# Circuit_Diagram.net
KiCad netlist of a schematic drawn in EAGLE
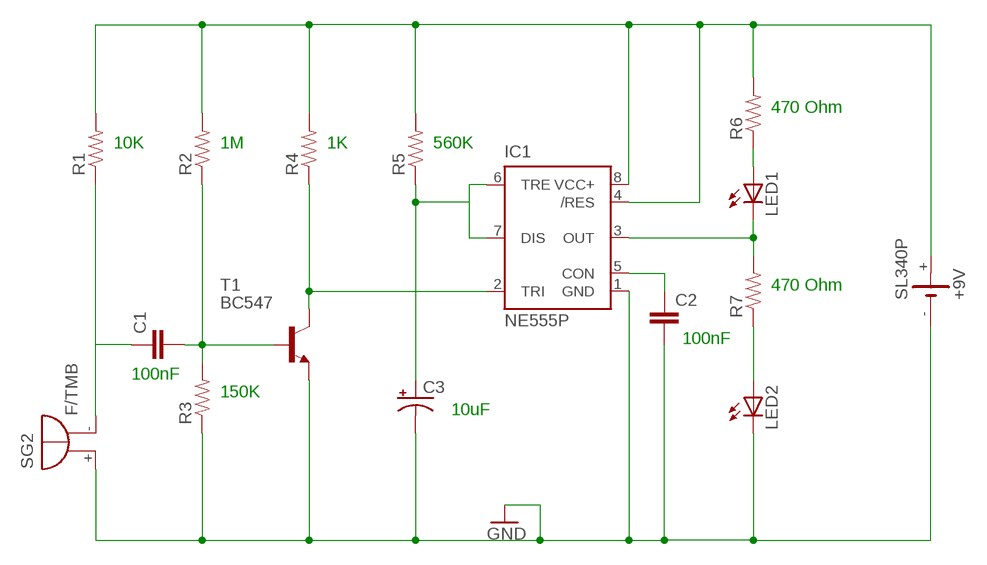
[diagram p0: schematic, sheet 1]

(export (version "E")
  (design (tool "Eeschema 10.0.6"))
  (components
    (comp (ref "+9V")
      (value "SL340P")
      (footprint "eagle-import:SL-340_P3.6V")
      (libsource (lib "eagle-import") (part "SL340P"))
    )
    (comp (ref "C1")
      (value "0.1UF-50V-20%(PTH)KIT-EZ")
      (footprint "eagle-import:CAP-PTH-SMALL-KIT")
      (libsource (lib "eagle-import") (part "0.1UF-50V-20%(PTH)KIT-EZ"))
    )
    (comp (ref "C2")
      (value "0.1UF-50V-20%(PTH)KIT-EZ")
      (footprint "eagle-import:CAP-PTH-SMALL-KIT")
      (libsource (lib "eagle-import") (part "0.1UF-50V-20%(PTH)KIT-EZ"))
    )
    (comp (ref "C3")
      (value "CAP_POLPTH1")
      (footprint "eagle-import:CPOL-RADIAL-100UF-25V")
      (libsource (lib "eagle-import") (part "CAP_POLPTH1"))
    )
    (comp (ref "IC1")
      (value "NE555P")
      (footprint "eagle-import:DIL-08")
      (fields (field (name "MF") "Arrow Electronics") (field (name "MPN") "NE555N"))
      (libsource (lib "eagle-import") (part "NE555P"))
    )
    (comp (ref "LED1")
      (value "LED5MM")
      (footprint "eagle-import:LED5MM")
      (libsource (lib "eagle-import") (part "LED5MM"))
    )
    (comp (ref "LED2")
      (value "LED5MM")
      (footprint "eagle-import:LED5MM")
      (libsource (lib "eagle-import") (part "LED5MM"))
    )
    (comp (ref "R1")
      (value "10KOHM1/6W5%(PTH)KIT")
      (footprint "eagle-import:AXIAL-0.3-KIT")
      (libsource (lib "eagle-import") (part "10KOHM1/6W5%(PTH)KIT"))
    )
    (comp (ref "R2")
      (value "10KOHM1/6W5%(PTH)KIT")
      (footprint "eagle-import:AXIAL-0.3-KIT")
      (libsource (lib "eagle-import") (part "10KOHM1/6W5%(PTH)KIT"))
    )
    (comp (ref "R3")
      (value "10KOHM1/6W5%(PTH)KIT")
      (footprint "eagle-import:AXIAL-0.3-KIT")
      (libsource (lib "eagle-import") (part "10KOHM1/6W5%(PTH)KIT"))
    )
    (comp (ref "R4")
      (value "10KOHM1/6W5%(PTH)KIT")
      (footprint "eagle-import:AXIAL-0.3-KIT")
      (libsource (lib "eagle-import") (part "10KOHM1/6W5%(PTH)KIT"))
    )
    (comp (ref "R5")
      (value "10KOHM1/6W5%(PTH)KIT")
      (footprint "eagle-import:AXIAL-0.3-KIT")
      (libsource (lib "eagle-import") (part "10KOHM1/6W5%(PTH)KIT"))
    )
    (comp (ref "R6")
      (value "10KOHM1/6W5%(PTH)KIT")
      (footprint "eagle-import:AXIAL-0.3-KIT")
      (libsource (lib "eagle-import") (part "10KOHM1/6W5%(PTH)KIT"))
    )
    (comp (ref "R7")
      (value "10KOHM1/6W5%(PTH)KIT")
      (footprint "eagle-import:AXIAL-0.3-KIT")
      (libsource (lib "eagle-import") (part "10KOHM1/6W5%(PTH)KIT"))
    )
    (comp (ref "SG2")
      (value "F/TMB")
      (footprint "eagle-import:F_TMB")
      (libsource (lib "eagle-import") (part "F/TMB"))
    )
    (comp (ref "T1")
      (value "BC547")
      (footprint "eagle-import:TO92")
      (libsource (lib "eagle-import") (part "BC547"))
    )
  )
  (nets
    (net (code "1") (name "GND") (class "Default")
      (node (ref "+9V") (pin "-") (pinfunction "-_-") (pintype "passive"))
      (node (ref "C2") (pin "2") (pinfunction "2_2") (pintype "passive"))
      (node (ref "C3") (pin "2") (pinfunction "-_2") (pintype "passive"))
      (node (ref "IC1") (pin "1") (pinfunction "GND_1") (pintype "power_in"))
      (node (ref "LED2") (pin "K") (pinfunction "C_K") (pintype "passive"))
      (node (ref "R3") (pin "P$1") (pinfunction "1_P$1") (pintype "passive"))
      (node (ref "SG2") (pin "+") (pinfunction "+_+") (pintype "passive"))
      (node (ref "T1") (pin "1") (pinfunction "E_1") (pintype "passive"))
    )
    (net (code "2") (name "Net-(C3-+)") (class "Default")
      (node (ref "C3") (pin "1") (pinfunction "+_1") (pintype "passive"))
      (node (ref "IC1") (pin "6") (pinfunction "TRE_6") (pintype "input"))
      (node (ref "IC1") (pin "7") (pinfunction "DIS_7") (pintype "input"))
      (node (ref "R5") (pin "P$1") (pinfunction "1_P$1") (pintype "passive"))
    )
    (net (code "3") (name "Net-(IC1-CON)") (class "Default")
      (node (ref "C2") (pin "1") (pinfunction "1_1") (pintype "passive"))
      (node (ref "IC1") (pin "5") (pinfunction "CON_5") (pintype "input"))
    )
    (net (code "4") (name "Net-(IC1-OUT)") (class "Default")
      (node (ref "IC1") (pin "3") (pinfunction "OUT_3") (pintype "output"))
      (node (ref "LED1") (pin "K") (pinfunction "C_K") (pintype "passive"))
      (node (ref "R7") (pin "P$2") (pinfunction "2_P$2") (pintype "passive"))
    )
    (net (code "5") (name "Net-(IC1-TRI)") (class "Default")
      (node (ref "IC1") (pin "2") (pinfunction "TRI_2") (pintype "input"))
      (node (ref "R4") (pin "P$1") (pinfunction "1_P$1") (pintype "passive"))
      (node (ref "T1") (pin "3") (pinfunction "C_3") (pintype "passive"))
    )
    (net (code "6") (name "Net-(IC1-VCC+)") (class "Default")
      (node (ref "+9V") (pin "+") (pinfunction "+_+") (pintype "passive"))
      (node (ref "IC1") (pin "4") (pinfunction "/RES_4") (pintype "input"))
      (node (ref "IC1") (pin "8") (pinfunction "VCC+_8") (pintype "power_in"))
      (node (ref "R1") (pin "P$2") (pinfunction "2_P$2") (pintype "passive"))
      (node (ref "R2") (pin "P$2") (pinfunction "2_P$2") (pintype "passive"))
      (node (ref "R4") (pin "P$2") (pinfunction "2_P$2") (pintype "passive"))
      (node (ref "R5") (pin "P$2") (pinfunction "2_P$2") (pintype "passive"))
      (node (ref "R6") (pin "P$2") (pinfunction "2_P$2") (pintype "passive"))
    )
    (net (code "7") (name "Net-(R1-1)") (class "Default")
      (node (ref "C1") (pin "1") (pinfunction "1_1") (pintype "passive"))
      (node (ref "R1") (pin "P$1") (pinfunction "1_P$1") (pintype "passive"))
      (node (ref "SG2") (pin "-") (pinfunction "-_-") (pintype "passive"))
    )
    (net (code "8") (name "Net-(R2-1)") (class "Default")
      (node (ref "C1") (pin "2") (pinfunction "2_2") (pintype "passive"))
      (node (ref "R2") (pin "P$1") (pinfunction "1_P$1") (pintype "passive"))
      (node (ref "R3") (pin "P$2") (pinfunction "2_P$2") (pintype "passive"))
      (node (ref "T1") (pin "2") (pinfunction "B_2") (pintype "passive"))
    )
    (net (code "9") (name "Net-(R6-1)") (class "Default")
      (node (ref "LED1") (pin "A") (pinfunction "A_A") (pintype "passive"))
      (node (ref "R6") (pin "P$1") (pinfunction "1_P$1") (pintype "passive"))
    )
    (net (code "10") (name "Net-(R7-1)") (class "Default")
      (node (ref "LED2") (pin "A") (pinfunction "A_A") (pintype "passive"))
      (node (ref "R7") (pin "P$1") (pinfunction "1_P$1") (pintype "passive"))
    )
  )
)
